# VL6180_Sensor.net
KiCad netlist of a schematic drawn in EAGLE
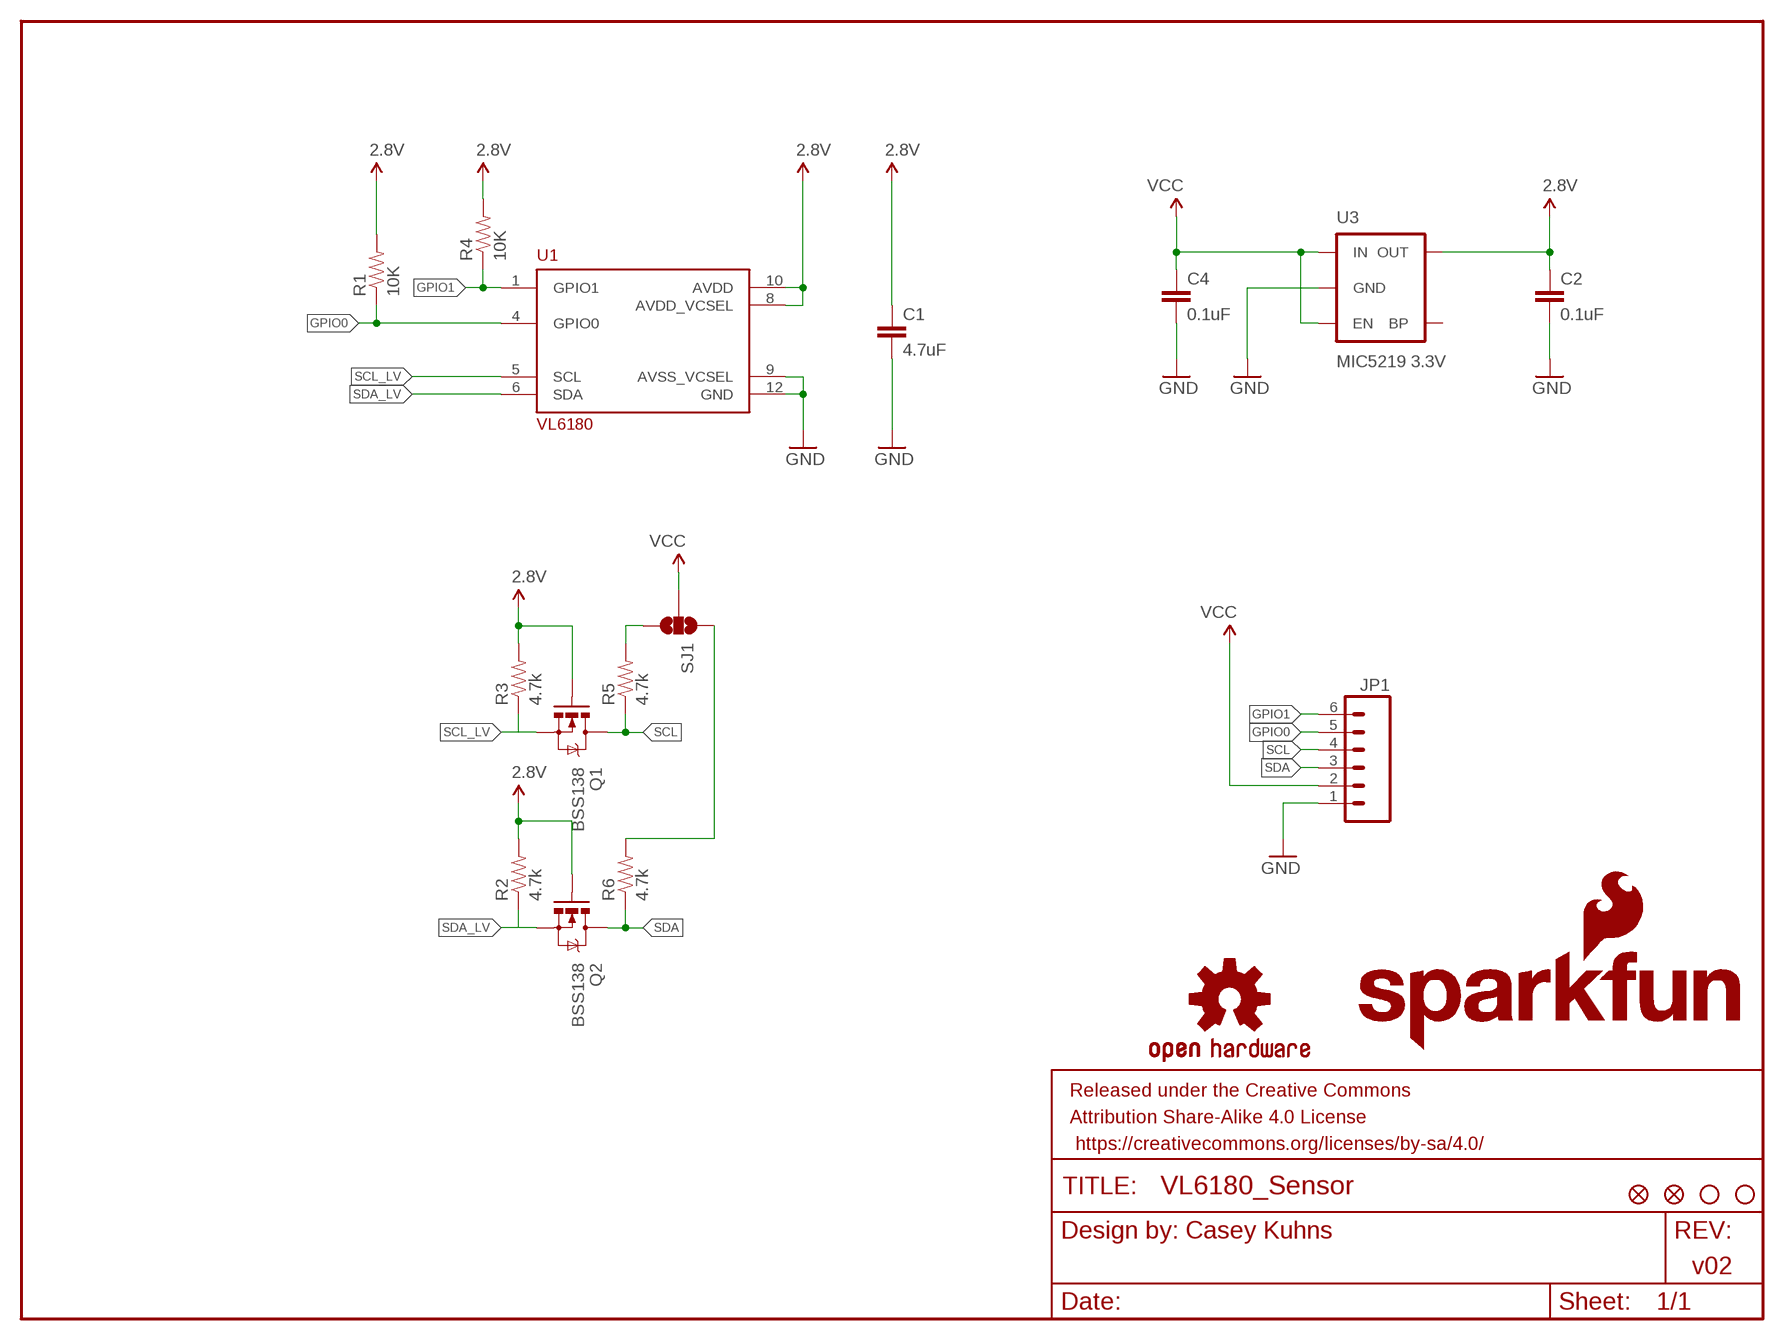
[diagram p0: schematic, sheet 1]

(export (version "E")
  (design (tool "Eeschema 10.0.6"))
  (components
    (comp (ref "C1")
      (value "4.7uF")
      (footprint "eagle-import:0603-CAP")
      (libsource (lib "eagle-import") (part "4.7UF-6.3V-10%(0603)0603"))
    )
    (comp (ref "C2")
      (value "0.1uF")
      (footprint "eagle-import:0603-CAP")
      (libsource (lib "eagle-import") (part "0.1UF-25V(+80/-20%)(0603)"))
    )
    (comp (ref "C4")
      (value "0.1uF")
      (footprint "eagle-import:0603-CAP")
      (libsource (lib "eagle-import") (part "0.1UF-25V(+80/-20%)(0603)"))
    )
    (comp (ref "FID1")
      (value "FIDUCIAL1X2")
      (footprint "eagle-import:FIDUCIAL-1X2")
      (libsource (lib "eagle-import") (part "FIDUCIAL1X2"))
    )
    (comp (ref "FID2")
      (value "FIDUCIAL1X2")
      (footprint "eagle-import:FIDUCIAL-1X2")
      (libsource (lib "eagle-import") (part "FIDUCIAL1X2"))
    )
    (comp (ref "FRAME1")
      (value "FRAME-LETTER")
      (footprint "eagle-import:CREATIVE_COMMONS")
      (libsource (lib "eagle-import") (part "FRAME-LETTER"))
    )
    (comp (ref "JP1")
      (value "M06SIP")
      (footprint "eagle-import:1X06")
      (libsource (lib "eagle-import") (part "M06SIP"))
    )
    (comp (ref "LOGO1")
      (value "SFE_LOGO_NAME_FLAME.1_INCH")
      (footprint "eagle-import:SFE_LOGO_NAME_FLAME_.1")
      (libsource (lib "eagle-import") (part "SFE_LOGO_NAME_FLAME.1_INCH"))
    )
    (comp (ref "LOGO2")
      (value "OSHW-LOGOS")
      (footprint "eagle-import:OSHW-LOGO-S")
      (libsource (lib "eagle-import") (part "OSHW-LOGOS"))
    )
    (comp (ref "Q1")
      (value "BSS138")
      (footprint "eagle-import:SOT23")
      (libsource (lib "eagle-import") (part "MOSFET-NCHANNELBSS138"))
    )
    (comp (ref "Q2")
      (value "BSS138")
      (footprint "eagle-import:SOT23")
      (libsource (lib "eagle-import") (part "MOSFET-NCHANNELBSS138"))
    )
    (comp (ref "R1")
      (value "10K")
      (footprint "eagle-import:0603-RES")
      (libsource (lib "eagle-import") (part "10KOHM1/10W1%(0603)0603"))
    )
    (comp (ref "R2")
      (value "4.7k")
      (footprint "eagle-import:0603")
      (libsource (lib "eagle-import") (part "4.7KOHM1/10W1%(0603)"))
    )
    (comp (ref "R3")
      (value "4.7k")
      (footprint "eagle-import:0603")
      (libsource (lib "eagle-import") (part "4.7KOHM1/10W1%(0603)"))
    )
    (comp (ref "R4")
      (value "10K")
      (footprint "eagle-import:0603-RES")
      (libsource (lib "eagle-import") (part "10KOHM1/10W1%(0603)0603"))
    )
    (comp (ref "R5")
      (value "4.7k")
      (footprint "eagle-import:0603")
      (libsource (lib "eagle-import") (part "4.7KOHM1/10W1%(0603)"))
    )
    (comp (ref "R6")
      (value "4.7k")
      (footprint "eagle-import:0603")
      (libsource (lib "eagle-import") (part "4.7KOHM1/10W1%(0603)"))
    )
    (comp (ref "SJ1")
      (value "SOLDERJUMPER_2WAYPASTE1&2&3")
      (footprint "eagle-import:SJ_3_PASTE1&2&3")
      (libsource (lib "eagle-import") (part "SOLDERJUMPER_2WAYPASTE1&2&3"))
    )
    (comp (ref "STANDOFF1")
      (value "STAND-OFF")
      (footprint "eagle-import:STAND-OFF")
      (libsource (lib "eagle-import") (part "STAND-OFF"))
    )
    (comp (ref "STANDOFF2")
      (value "STAND-OFF")
      (footprint "eagle-import:STAND-OFF")
      (libsource (lib "eagle-import") (part "STAND-OFF"))
    )
    (comp (ref "U1")
      (value "VL6180")
      (footprint "eagle-import:VL6180")
      (libsource (lib "eagle-import") (part "VL6180"))
    )
    (comp (ref "U3")
      (value "MIC5219 3.3V")
      (footprint "eagle-import:SOT23-5")
      (libsource (lib "eagle-import") (part "V_REG_MIC52193.3V"))
    )
  )
  (nets
    (net (code "1") (name "2.8V") (class "Default")
      (node (ref "C1") (pin "1") (pinfunction "1_1") (pintype "passive"))
      (node (ref "C2") (pin "1") (pinfunction "1_1") (pintype "passive"))
      (node (ref "Q1") (pin "1") (pinfunction "G_1") (pintype "passive"))
      (node (ref "Q2") (pin "1") (pinfunction "G_1") (pintype "passive"))
      (node (ref "R1") (pin "2") (pinfunction "2_2") (pintype "passive"))
      (node (ref "R2") (pin "2") (pinfunction "2_2") (pintype "passive"))
      (node (ref "R3") (pin "2") (pinfunction "2_2") (pintype "passive"))
      (node (ref "R4") (pin "2") (pinfunction "2_2") (pintype "passive"))
      (node (ref "U1") (pin "10") (pinfunction "AVDD_10") (pintype "bidirectional"))
      (node (ref "U1") (pin "8") (pinfunction "AVDD_VCSEL_8") (pintype "bidirectional"))
      (node (ref "U3") (pin "5") (pinfunction "OUT_5") (pintype "passive"))
    )
    (net (code "2") (name "GND") (class "Default")
      (node (ref "C1") (pin "2") (pinfunction "2_2") (pintype "passive"))
      (node (ref "C2") (pin "2") (pinfunction "2_2") (pintype "passive"))
      (node (ref "C4") (pin "2") (pinfunction "2_2") (pintype "passive"))
      (node (ref "JP1") (pin "1") (pinfunction "1_1") (pintype "passive"))
      (node (ref "U1") (pin "12") (pinfunction "GND_12") (pintype "bidirectional"))
      (node (ref "U1") (pin "9") (pinfunction "AVSS_VCSEL_9") (pintype "bidirectional"))
      (node (ref "U3") (pin "2") (pinfunction "GND_2") (pintype "input"))
    )
    (net (code "3") (name "GPIO0") (class "Default")
      (node (ref "JP1") (pin "5") (pinfunction "5_5") (pintype "passive"))
      (node (ref "R1") (pin "1") (pinfunction "1_1") (pintype "passive"))
      (node (ref "U1") (pin "4") (pinfunction "GPIO0_4") (pintype "bidirectional"))
    )
    (net (code "4") (name "GPIO1") (class "Default")
      (node (ref "JP1") (pin "6") (pinfunction "6_6") (pintype "passive"))
      (node (ref "R4") (pin "1") (pinfunction "1_1") (pintype "passive"))
      (node (ref "U1") (pin "1") (pinfunction "GPIO1_1") (pintype "bidirectional"))
    )
    (net (code "5") (name "Net-(R5-Pad2)") (class "Default")
      (node (ref "R5") (pin "2") (pinfunction "2_2") (pintype "passive"))
      (node (ref "SJ1") (pin "3") (pinfunction "3_3") (pintype "passive"))
    )
    (net (code "6") (name "Net-(R6-Pad2)") (class "Default")
      (node (ref "R6") (pin "2") (pinfunction "2_2") (pintype "passive"))
      (node (ref "SJ1") (pin "1") (pinfunction "1_1") (pintype "passive"))
    )
    (net (code "7") (name "SCL") (class "Default")
      (node (ref "JP1") (pin "4") (pinfunction "4_4") (pintype "passive"))
      (node (ref "Q1") (pin "3") (pinfunction "D_3") (pintype "passive"))
      (node (ref "R5") (pin "1") (pinfunction "1_1") (pintype "passive"))
    )
    (net (code "8") (name "SCL_LV") (class "Default")
      (node (ref "Q1") (pin "2") (pinfunction "S_2") (pintype "passive"))
      (node (ref "R3") (pin "1") (pinfunction "1_1") (pintype "passive"))
      (node (ref "U1") (pin "5") (pinfunction "SCL_5") (pintype "bidirectional"))
    )
    (net (code "9") (name "SDA") (class "Default")
      (node (ref "JP1") (pin "3") (pinfunction "3_3") (pintype "passive"))
      (node (ref "Q2") (pin "3") (pinfunction "D_3") (pintype "passive"))
      (node (ref "R6") (pin "1") (pinfunction "1_1") (pintype "passive"))
    )
    (net (code "10") (name "SDA_LV") (class "Default")
      (node (ref "Q2") (pin "2") (pinfunction "S_2") (pintype "passive"))
      (node (ref "R2") (pin "1") (pinfunction "1_1") (pintype "passive"))
      (node (ref "U1") (pin "6") (pinfunction "SDA_6") (pintype "bidirectional"))
    )
    (net (code "11") (name "VCC") (class "Default")
      (node (ref "C4") (pin "1") (pinfunction "1_1") (pintype "passive"))
      (node (ref "JP1") (pin "2") (pinfunction "2_2") (pintype "passive"))
      (node (ref "SJ1") (pin "2") (pinfunction "2_2") (pintype "passive"))
      (node (ref "U3") (pin "1") (pinfunction "IN_1") (pintype "input"))
      (node (ref "U3") (pin "3") (pinfunction "EN_3") (pintype "input"))
    )
    (net (code "12") (name "unconnected-(U3-BP-Pad4)") (class "Default")
      (node (ref "U3") (pin "4") (pinfunction "BP_4") (pintype "input"))
    )
  )
)
